# TH8_AFE.net
KiCad netlist of a schematic drawn in Altium Designer
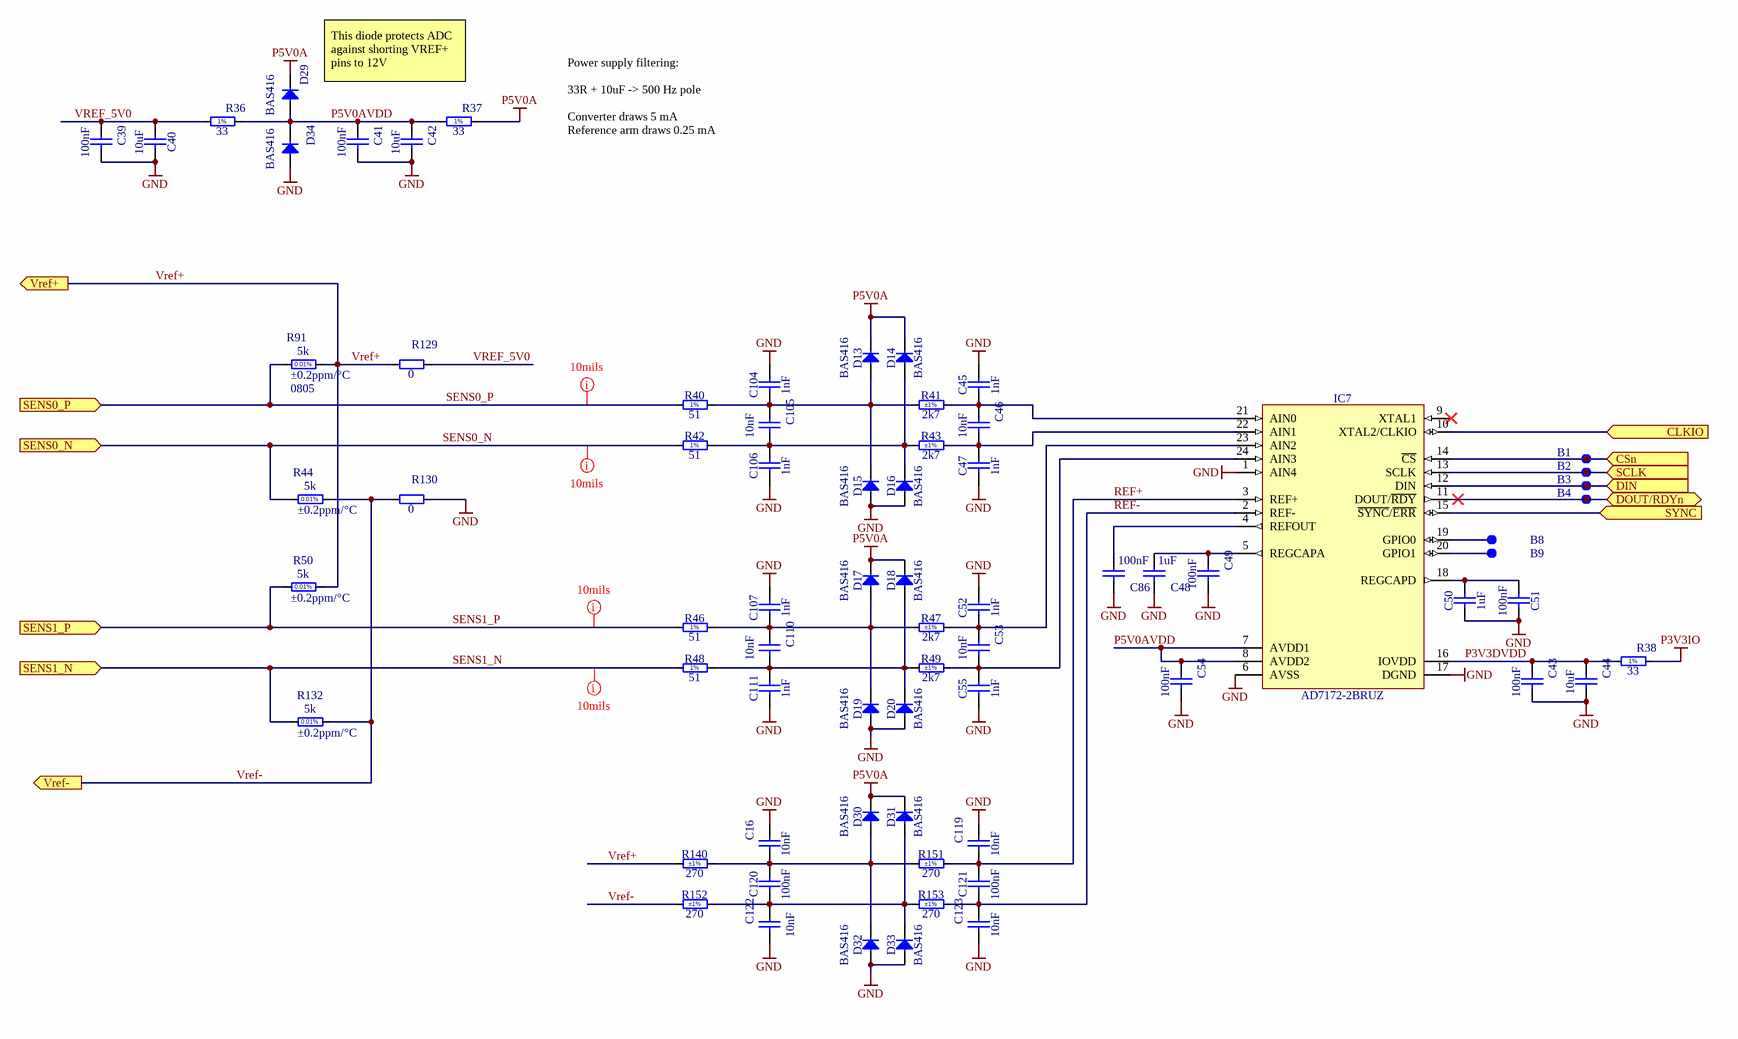
[diagram p0: TH8_AFE.SchDoc]

(export (version "E")
  (design (tool "Eeschema 10.0.6"))
  (components
    (comp (ref "B1")
      (value "SMD Pad")
      (footprint "C100")
      (description "Through Hole Pad")
      (fields (field (name "PART NUMBER") "SMD_PAD_D1MM") (field (name "AUTHOR") "CERN DEM JLC"))
      (libsource (lib "Eletro-mechanical") (part "Single SMD Pad (Round)"))
    )
    (comp (ref "B2")
      (value "SMD Pad")
      (footprint "C100")
      (description "Through Hole Pad")
      (fields (field (name "PART NUMBER") "SMD_PAD_D1MM") (field (name "AUTHOR") "CERN DEM JLC"))
      (libsource (lib "Eletro-mechanical") (part "Single SMD Pad (Round)"))
    )
    (comp (ref "B3")
      (value "SMD Pad")
      (footprint "C100")
      (description "Through Hole Pad")
      (fields (field (name "PART NUMBER") "SMD_PAD_D1MM") (field (name "AUTHOR") "CERN DEM JLC"))
      (libsource (lib "Eletro-mechanical") (part "Single SMD Pad (Round)"))
    )
    (comp (ref "B4")
      (value "SMD Pad")
      (footprint "C100")
      (description "Through Hole Pad")
      (fields (field (name "PART NUMBER") "SMD_PAD_D1MM") (field (name "AUTHOR") "CERN DEM JLC"))
      (libsource (lib "Eletro-mechanical") (part "Single SMD Pad (Round)"))
    )
    (comp (ref "B8")
      (value "SMD Pad")
      (footprint "C100")
      (description "Through Hole Pad")
      (fields (field (name "PART NUMBER") "SMD_PAD_D1MM") (field (name "AUTHOR") "CERN DEM JLC"))
      (libsource (lib "Eletro-mechanical") (part "Single SMD Pad (Round)"))
    )
    (comp (ref "B9")
      (value "SMD Pad")
      (footprint "C100")
      (description "Through Hole Pad")
      (fields (field (name "PART NUMBER") "SMD_PAD_D1MM") (field (name "AUTHOR") "CERN DEM JLC"))
      (libsource (lib "Eletro-mechanical") (part "Single SMD Pad (Round)"))
    )
    (comp (ref "C16")
      (value "10nF")
      (footprint "CAPC1608X87N")
      (description "Non-polarised capacitor")
      (fields
        (field (name "PART NUMBER") "CC0603_10NF_50V_5%_C0G")
        (field (name "VOLTAGE") "50V")
        (field (name "AUTHOR") "CERN DEM JLC")
      )
      (libsource (lib "Capacitors") (part "Capacitor - non polarized"))
    )
    (comp (ref "C39")
      (value "100nF")
      (footprint "CAPC1005X55N")
      (description "Non-polarised capacitor")
      (fields
        (field (name "PART NUMBER") "CC0402_100NF_16V_10%_X5R")
        (field (name "VOLTAGE") "16V")
        (field (name "AUTHOR") "CERN DEM JLC")
      )
      (libsource (lib "Capacitors") (part "Capacitor - non polarized"))
    )
    (comp (ref "C40")
      (value "10uF")
      (footprint "CAPC2012X135N")
      (description "Non-polarised capacitor")
      (fields
        (field (name "PART NUMBER") "CC0805_10UF_16V_10%_X5R")
        (field (name "VOLTAGE") "16V")
        (field (name "AUTHOR") "CERN DEM JLC")
      )
      (libsource (lib "Capacitors") (part "Capacitor - non polarized"))
    )
    (comp (ref "C41")
      (value "100nF")
      (footprint "CAPC1005X55N")
      (description "Non-polarised capacitor")
      (fields
        (field (name "PART NUMBER") "CC0402_100NF_16V_10%_X5R")
        (field (name "VOLTAGE") "16V")
        (field (name "AUTHOR") "CERN DEM JLC")
      )
      (libsource (lib "Capacitors") (part "Capacitor - non polarized"))
    )
    (comp (ref "C42")
      (value "10uF")
      (footprint "CAPC2012X135N")
      (description "Non-polarised capacitor")
      (fields
        (field (name "PART NUMBER") "CC0805_10UF_16V_10%_X5R")
        (field (name "VOLTAGE") "16V")
        (field (name "AUTHOR") "CERN DEM JLC")
      )
      (libsource (lib "Capacitors") (part "Capacitor - non polarized"))
    )
    (comp (ref "C43")
      (value "100nF")
      (footprint "CAPC1005X55N")
      (description "Non-polarised capacitor")
      (fields
        (field (name "PART NUMBER") "CC0402_100NF_16V_10%_X5R")
        (field (name "VOLTAGE") "16V")
        (field (name "AUTHOR") "CERN DEM JLC")
      )
      (libsource (lib "Capacitors") (part "Capacitor - non polarized"))
    )
    (comp (ref "C44")
      (value "10uF")
      (footprint "CAPC2012X135N")
      (description "Non-polarised capacitor")
      (fields
        (field (name "PART NUMBER") "CC0805_10UF_16V_10%_X5R")
        (field (name "VOLTAGE") "16V")
        (field (name "AUTHOR") "CERN DEM JLC")
      )
      (libsource (lib "Capacitors") (part "Capacitor - non polarized"))
    )
    (comp (ref "C45")
      (value "1nF")
      (footprint "CAPC1608X90N")
      (description "Non-polarised capacitor")
      (fields
        (field (name "PART NUMBER") "CC0603_1NF_50V_5%_NP0")
        (field (name "VOLTAGE") "50V")
        (field (name "AUTHOR") "CERN DEM JLC")
      )
      (libsource (lib "Capacitors") (part "Capacitor - non polarized"))
    )
    (comp (ref "C46")
      (value "10nF")
      (footprint "CAPC1608X87N")
      (description "Non-polarised capacitor")
      (fields
        (field (name "PART NUMBER") "CC0603_10NF_50V_5%_C0G")
        (field (name "VOLTAGE") "50V")
        (field (name "AUTHOR") "CERN DEM JLC")
      )
      (libsource (lib "Capacitors") (part "Capacitor - non polarized"))
    )
    (comp (ref "C47")
      (value "1nF")
      (footprint "CAPC1608X90N")
      (description "Non-polarised capacitor")
      (fields
        (field (name "PART NUMBER") "CC0603_1NF_50V_5%_NP0")
        (field (name "VOLTAGE") "50V")
        (field (name "AUTHOR") "CERN DEM JLC")
      )
      (libsource (lib "Capacitors") (part "Capacitor - non polarized"))
    )
    (comp (ref "C48")
      (value "1uF")
      (footprint "CAPC1608X87N")
      (description "Non-polarised capacitor")
      (fields
        (field (name "PART NUMBER") "CC0603_1UF_25V_10%_X7R")
        (field (name "VOLTAGE") "25V")
        (field (name "AUTHOR") "CERN DEM JLC")
      )
      (libsource (lib "Capacitors") (part "Capacitor - non polarized"))
    )
    (comp (ref "C49")
      (value "100nF")
      (footprint "CAPC1005X55N")
      (description "Non-polarised capacitor")
      (fields
        (field (name "PART NUMBER") "CC0402_100NF_16V_10%_X5R")
        (field (name "VOLTAGE") "16V")
        (field (name "AUTHOR") "CERN DEM JLC")
      )
      (libsource (lib "Capacitors") (part "Capacitor - non polarized"))
    )
    (comp (ref "C50")
      (value "1uF")
      (footprint "CAPC1608X87N")
      (description "Non-polarised capacitor")
      (fields
        (field (name "PART NUMBER") "CC0603_1UF_25V_10%_X7R")
        (field (name "VOLTAGE") "25V")
        (field (name "AUTHOR") "CERN DEM JLC")
      )
      (libsource (lib "Capacitors") (part "Capacitor - non polarized"))
    )
    (comp (ref "C51")
      (value "100nF")
      (footprint "CAPC1005X55N")
      (description "Non-polarised capacitor")
      (fields
        (field (name "PART NUMBER") "CC0402_100NF_16V_10%_X5R")
        (field (name "VOLTAGE") "16V")
        (field (name "AUTHOR") "CERN DEM JLC")
      )
      (libsource (lib "Capacitors") (part "Capacitor - non polarized"))
    )
    (comp (ref "C52")
      (value "1nF")
      (footprint "CAPC1608X90N")
      (description "Non-polarised capacitor")
      (fields
        (field (name "PART NUMBER") "CC0603_1NF_50V_5%_NP0")
        (field (name "VOLTAGE") "50V")
        (field (name "AUTHOR") "CERN DEM JLC")
      )
      (libsource (lib "Capacitors") (part "Capacitor - non polarized"))
    )
    (comp (ref "C53")
      (value "10nF")
      (footprint "CAPC1608X87N")
      (description "Non-polarised capacitor")
      (fields
        (field (name "PART NUMBER") "CC0603_10NF_50V_5%_C0G")
        (field (name "VOLTAGE") "50V")
        (field (name "AUTHOR") "CERN DEM JLC")
      )
      (libsource (lib "Capacitors") (part "Capacitor - non polarized"))
    )
    (comp (ref "C54")
      (value "100nF")
      (footprint "CAPC1005X55N")
      (description "Non-polarised capacitor")
      (fields
        (field (name "PART NUMBER") "CC0402_100NF_16V_10%_X5R")
        (field (name "VOLTAGE") "16V")
        (field (name "AUTHOR") "CERN DEM JLC")
      )
      (libsource (lib "Capacitors") (part "Capacitor - non polarized"))
    )
    (comp (ref "C55")
      (value "1nF")
      (footprint "CAPC1608X90N")
      (description "Non-polarised capacitor")
      (fields
        (field (name "PART NUMBER") "CC0603_1NF_50V_5%_NP0")
        (field (name "VOLTAGE") "50V")
        (field (name "AUTHOR") "CERN DEM JLC")
      )
      (libsource (lib "Capacitors") (part "Capacitor - non polarized"))
    )
    (comp (ref "C86")
      (value "100nF")
      (footprint "CAPC1005X55N")
      (description "Non-polarised capacitor")
      (fields
        (field (name "PART NUMBER") "CC0402_100NF_16V_10%_X5R")
        (field (name "VOLTAGE") "16V")
        (field (name "AUTHOR") "CERN DEM JLC")
      )
      (libsource (lib "Capacitors") (part "Capacitor - non polarized"))
    )
    (comp (ref "C104")
      (value "1nF")
      (footprint "CAPC1608X90N")
      (description "Non-polarised capacitor")
      (fields
        (field (name "PART NUMBER") "CC0603_1NF_50V_5%_NP0")
        (field (name "VOLTAGE") "50V")
        (field (name "AUTHOR") "CERN DEM JLC")
      )
      (libsource (lib "Capacitors") (part "Capacitor - non polarized"))
    )
    (comp (ref "C105")
      (value "10nF")
      (footprint "CAPC1608X87N")
      (description "Non-polarised capacitor")
      (fields
        (field (name "PART NUMBER") "CC0603_10NF_50V_5%_C0G")
        (field (name "VOLTAGE") "50V")
        (field (name "AUTHOR") "CERN DEM JLC")
      )
      (libsource (lib "Capacitors") (part "Capacitor - non polarized"))
    )
    (comp (ref "C106")
      (value "1nF")
      (footprint "CAPC1608X90N")
      (description "Non-polarised capacitor")
      (fields
        (field (name "PART NUMBER") "CC0603_1NF_50V_5%_NP0")
        (field (name "VOLTAGE") "50V")
        (field (name "AUTHOR") "CERN DEM JLC")
      )
      (libsource (lib "Capacitors") (part "Capacitor - non polarized"))
    )
    (comp (ref "C107")
      (value "1nF")
      (footprint "CAPC1608X90N")
      (description "Non-polarised capacitor")
      (fields
        (field (name "PART NUMBER") "CC0603_1NF_50V_5%_NP0")
        (field (name "VOLTAGE") "50V")
        (field (name "AUTHOR") "CERN DEM JLC")
      )
      (libsource (lib "Capacitors") (part "Capacitor - non polarized"))
    )
    (comp (ref "C110")
      (value "10nF")
      (footprint "CAPC1608X87N")
      (description "Non-polarised capacitor")
      (fields
        (field (name "PART NUMBER") "CC0603_10NF_50V_5%_C0G")
        (field (name "VOLTAGE") "50V")
        (field (name "AUTHOR") "CERN DEM JLC")
      )
      (libsource (lib "Capacitors") (part "Capacitor - non polarized"))
    )
    (comp (ref "C111")
      (value "1nF")
      (footprint "CAPC1608X90N")
      (description "Non-polarised capacitor")
      (fields
        (field (name "PART NUMBER") "CC0603_1NF_50V_5%_NP0")
        (field (name "VOLTAGE") "50V")
        (field (name "AUTHOR") "CERN DEM JLC")
      )
      (libsource (lib "Capacitors") (part "Capacitor - non polarized"))
    )
    (comp (ref "C119")
      (value "10nF")
      (footprint "CAPC1608X87N")
      (description "Non-polarised capacitor")
      (fields
        (field (name "PART NUMBER") "CC0603_10NF_50V_5%_C0G")
        (field (name "VOLTAGE") "50V")
        (field (name "AUTHOR") "CERN DEM JLC")
      )
      (libsource (lib "Capacitors") (part "Capacitor - non polarized"))
    )
    (comp (ref "C120")
      (value "100nF")
      (footprint "CAPC1608X87N")
      (description "Non-polarised capacitor")
      (fields
        (field (name "PART NUMBER") "CC0603_100NF_50V_10%_X5R")
        (field (name "VOLTAGE") "50V")
        (field (name "AUTHOR") "CERN DEM MR")
      )
      (libsource (lib "Capacitors") (part "Capacitor - non polarized"))
    )
    (comp (ref "C121")
      (value "100nF")
      (footprint "CAPC1608X87N")
      (description "Non-polarised capacitor")
      (fields
        (field (name "PART NUMBER") "CC0603_100NF_50V_10%_X5R")
        (field (name "VOLTAGE") "50V")
        (field (name "AUTHOR") "CERN DEM MR")
      )
      (libsource (lib "Capacitors") (part "Capacitor - non polarized"))
    )
    (comp (ref "C122")
      (value "10nF")
      (footprint "CAPC1608X87N")
      (description "Non-polarised capacitor")
      (fields
        (field (name "PART NUMBER") "CC0603_10NF_50V_5%_C0G")
        (field (name "VOLTAGE") "50V")
        (field (name "AUTHOR") "CERN DEM JLC")
      )
      (libsource (lib "Capacitors") (part "Capacitor - non polarized"))
    )
    (comp (ref "C123")
      (value "10nF")
      (footprint "CAPC1608X87N")
      (description "Non-polarised capacitor")
      (fields
        (field (name "PART NUMBER") "CC0603_10NF_50V_5%_C0G")
        (field (name "VOLTAGE") "50V")
        (field (name "AUTHOR") "CERN DEM JLC")
      )
      (libsource (lib "Capacitors") (part "Capacitor - non polarized"))
    )
    (comp (ref "D13")
      (value "BAS416")
      (footprint "SOD2512X110N")
      (description "Diode")
      (fields
        (field (name "VOLTAGE") "75V")
        (field (name "POWER") "200mA")
        (field (name "AUTHOR") "CERN DEM JLC")
      )
      (libsource (lib "ICs And Semiconductors") (part "Diode"))
    )
    (comp (ref "D14")
      (value "BAS416")
      (footprint "SOD2512X110N")
      (description "Diode")
      (fields
        (field (name "VOLTAGE") "75V")
        (field (name "POWER") "200mA")
        (field (name "AUTHOR") "CERN DEM JLC")
      )
      (libsource (lib "ICs And Semiconductors") (part "Diode"))
    )
    (comp (ref "D15")
      (value "BAS416")
      (footprint "SOD2512X110N")
      (description "Diode")
      (fields
        (field (name "VOLTAGE") "75V")
        (field (name "POWER") "200mA")
        (field (name "AUTHOR") "CERN DEM JLC")
      )
      (libsource (lib "ICs And Semiconductors") (part "Diode"))
    )
    (comp (ref "D16")
      (value "BAS416")
      (footprint "SOD2512X110N")
      (description "Diode")
      (fields
        (field (name "VOLTAGE") "75V")
        (field (name "POWER") "200mA")
        (field (name "AUTHOR") "CERN DEM JLC")
      )
      (libsource (lib "ICs And Semiconductors") (part "Diode"))
    )
    (comp (ref "D17")
      (value "BAS416")
      (footprint "SOD2512X110N")
      (description "Diode")
      (fields
        (field (name "VOLTAGE") "75V")
        (field (name "POWER") "200mA")
        (field (name "AUTHOR") "CERN DEM JLC")
      )
      (libsource (lib "ICs And Semiconductors") (part "Diode"))
    )
    (comp (ref "D18")
      (value "BAS416")
      (footprint "SOD2512X110N")
      (description "Diode")
      (fields
        (field (name "VOLTAGE") "75V")
        (field (name "POWER") "200mA")
        (field (name "AUTHOR") "CERN DEM JLC")
      )
      (libsource (lib "ICs And Semiconductors") (part "Diode"))
    )
    (comp (ref "D19")
      (value "BAS416")
      (footprint "SOD2512X110N")
      (description "Diode")
      (fields
        (field (name "VOLTAGE") "75V")
        (field (name "POWER") "200mA")
        (field (name "AUTHOR") "CERN DEM JLC")
      )
      (libsource (lib "ICs And Semiconductors") (part "Diode"))
    )
    (comp (ref "D20")
      (value "BAS416")
      (footprint "SOD2512X110N")
      (description "Diode")
      (fields
        (field (name "VOLTAGE") "75V")
        (field (name "POWER") "200mA")
        (field (name "AUTHOR") "CERN DEM JLC")
      )
      (libsource (lib "ICs And Semiconductors") (part "Diode"))
    )
    (comp (ref "D29")
      (value "BAS416")
      (footprint "SOD2512X110N")
      (description "Diode")
      (fields
        (field (name "VOLTAGE") "75V")
        (field (name "POWER") "200mA")
        (field (name "AUTHOR") "CERN DEM JLC")
      )
      (libsource (lib "ICs And Semiconductors") (part "Diode"))
    )
    (comp (ref "D30")
      (value "BAS416")
      (footprint "SOD2512X110N")
      (description "Diode")
      (fields
        (field (name "VOLTAGE") "75V")
        (field (name "POWER") "200mA")
        (field (name "AUTHOR") "CERN DEM JLC")
      )
      (libsource (lib "ICs And Semiconductors") (part "Diode"))
    )
    (comp (ref "D31")
      (value "BAS416")
      (footprint "SOD2512X110N")
      (description "Diode")
      (fields
        (field (name "VOLTAGE") "75V")
        (field (name "POWER") "200mA")
        (field (name "AUTHOR") "CERN DEM JLC")
      )
      (libsource (lib "ICs And Semiconductors") (part "Diode"))
    )
    (comp (ref "D32")
      (value "BAS416")
      (footprint "SOD2512X110N")
      (description "Diode")
      (fields
        (field (name "VOLTAGE") "75V")
        (field (name "POWER") "200mA")
        (field (name "AUTHOR") "CERN DEM JLC")
      )
      (libsource (lib "ICs And Semiconductors") (part "Diode"))
    )
    (comp (ref "D33")
      (value "BAS416")
      (footprint "SOD2512X110N")
      (description "Diode")
      (fields
        (field (name "VOLTAGE") "75V")
        (field (name "POWER") "200mA")
        (field (name "AUTHOR") "CERN DEM JLC")
      )
      (libsource (lib "ICs And Semiconductors") (part "Diode"))
    )
    (comp (ref "D34")
      (value "BAS416")
      (footprint "SOD2512X110N")
      (description "Diode")
      (fields
        (field (name "VOLTAGE") "75V")
        (field (name "POWER") "200mA")
        (field (name "AUTHOR") "CERN DEM JLC")
      )
      (libsource (lib "ICs And Semiconductors") (part "Diode"))
    )
    (comp (ref "IC7")
      (value "AD7172-2BRUZ")
      (footprint "SOP65P640X120-24N")
      (description "32-Bit, 10 kSPS, Sigma-Delta ADC with 100 µs Settling and True Rail-to-Rail Buffers")
      (fields (field (name "MANUFACTURER") "ANALOG DEVICES") (field (name "AUTHOR") "GK"))
      (libsource (lib "LIBRARY_SCH") (part "ADC_AD7172-2"))
    )
    (comp (ref "R36")
      (value "33")
      (footprint "RESC1005X40N")
      (description "Resistor - 1%")
      (fields
        (field (name "PART NUMBER") "R0402_33R_1%_0.0625W_100PPM")
        (field (name "POWER") "0.0625W")
        (field (name "AUTHOR") "CERN DEM JLC")
      )
      (libsource (lib "Resistors") (part "Resistor - 1%"))
    )
    (comp (ref "R37")
      (value "33")
      (footprint "RESC1005X40N")
      (description "Resistor - 1%")
      (fields
        (field (name "PART NUMBER") "R0402_33R_1%_0.0625W_100PPM")
        (field (name "POWER") "0.0625W")
        (field (name "AUTHOR") "CERN DEM JLC")
      )
      (libsource (lib "Resistors") (part "Resistor - 1%"))
    )
    (comp (ref "R38")
      (value "33")
      (footprint "RESC1005X40N")
      (description "Resistor - 1%")
      (fields
        (field (name "PART NUMBER") "R0402_33R_1%_0.0625W_100PPM")
        (field (name "POWER") "0.0625W")
        (field (name "AUTHOR") "CERN DEM JLC")
      )
      (libsource (lib "Resistors") (part "Resistor - 1%"))
    )
    (comp (ref "R40")
      (value "51")
      (footprint "RESC1005X40N")
      (description "Resistor - 1%")
      (fields
        (field (name "PART NUMBER") "R0402_51R_1%_0.0625W_100PPM")
        (field (name "POWER") "0.0625W")
        (field (name "AUTHOR") "CERN DEM JLC")
      )
      (libsource (lib "Resistors") (part "Resistor - 1%"))
    )
    (comp (ref "R41")
      (value "2k7")
      (footprint "RESC1005X40N")
      (description "Resistor - 1%")
      (fields
        (field (name "TOLERANCE") "±1%")
        (field (name "PART NUMBER") "R0402_2K7_1%_0.0625W_100PPM")
        (field (name "POWER") "0.0625W")
        (field (name "AUTHOR") "CERN DEM JLC")
      )
      (libsource (lib "Resistors") (part "Resistor - 1%"))
    )
    (comp (ref "R42")
      (value "51")
      (footprint "RESC1005X40N")
      (description "Resistor - 1%")
      (fields
        (field (name "PART NUMBER") "R0402_51R_1%_0.0625W_100PPM")
        (field (name "POWER") "0.0625W")
        (field (name "AUTHOR") "CERN DEM JLC")
      )
      (libsource (lib "Resistors") (part "Resistor - 1%"))
    )
    (comp (ref "R43")
      (value "2k7")
      (footprint "RESC1005X40N")
      (description "Resistor - 1%")
      (fields
        (field (name "TOLERANCE") "±1%")
        (field (name "PART NUMBER") "R0402_2K7_1%_0.0625W_100PPM")
        (field (name "POWER") "0.0625W")
        (field (name "AUTHOR") "CERN DEM JLC")
      )
      (libsource (lib "Resistors") (part "Resistor - 1%"))
    )
    (comp (ref "R44")
      (value "5k")
      (footprint "RESC2013X64N")
      (description "Resistor - 0.01%")
      (fields
        (field (name "PART NUMBER") "R0805_5K_0.01%_0.2W_0.2PPM_VISHAY_VSMP")
        (field (name "POWER") "0.2W")
        (field (name "TC") "±0.2ppm/°C")
        (field (name "AUTHOR") "CERN DEM JLC")
      )
      (libsource (lib "Resistors") (part "Resistor - 0.01%"))
    )
    (comp (ref "R46")
      (value "51")
      (footprint "RESC1005X40N")
      (description "Resistor - 1%")
      (fields
        (field (name "PART NUMBER") "R0402_51R_1%_0.0625W_100PPM")
        (field (name "POWER") "0.0625W")
        (field (name "AUTHOR") "CERN DEM JLC")
      )
      (libsource (lib "Resistors") (part "Resistor - 1%"))
    )
    (comp (ref "R47")
      (value "2k7")
      (footprint "RESC1005X40N")
      (description "Resistor - 1%")
      (fields
        (field (name "TOLERANCE") "±1%")
        (field (name "PART NUMBER") "R0402_2K7_1%_0.0625W_100PPM")
        (field (name "POWER") "0.0625W")
        (field (name "AUTHOR") "CERN DEM JLC")
      )
      (libsource (lib "Resistors") (part "Resistor - 1%"))
    )
    (comp (ref "R48")
      (value "51")
      (footprint "RESC1005X40N")
      (description "Resistor - 1%")
      (fields
        (field (name "PART NUMBER") "R0402_51R_1%_0.0625W_100PPM")
        (field (name "POWER") "0.0625W")
        (field (name "AUTHOR") "CERN DEM JLC")
      )
      (libsource (lib "Resistors") (part "Resistor - 1%"))
    )
    (comp (ref "R49")
      (value "2k7")
      (footprint "RESC1005X40N")
      (description "Resistor - 1%")
      (fields
        (field (name "TOLERANCE") "±1%")
        (field (name "PART NUMBER") "R0402_2K7_1%_0.0625W_100PPM")
        (field (name "POWER") "0.0625W")
        (field (name "AUTHOR") "CERN DEM JLC")
      )
      (libsource (lib "Resistors") (part "Resistor - 1%"))
    )
    (comp (ref "R50")
      (value "5k")
      (footprint "RESC2013X64N")
      (description "Resistor - 0.01%")
      (fields
        (field (name "PART NUMBER") "R0805_5K_0.01%_0.2W_0.2PPM_VISHAY_VSMP")
        (field (name "POWER") "0.2W")
        (field (name "TC") "±0.2ppm/°C")
        (field (name "AUTHOR") "CERN DEM JLC")
      )
      (libsource (lib "Resistors") (part "Resistor - 0.01%"))
    )
    (comp (ref "R91")
      (value "5k")
      (footprint "RESC2013X64N")
      (description "Resistor - 0.01%")
      (fields
        (field (name "PART NUMBER") "R0805_5K_0.01%_0.2W_0.2PPM_VISHAY_VSMP")
        (field (name "POWER") "0.2W")
        (field (name "TC") "±0.2ppm/°C")
        (field (name "CASE") "0805")
        (field (name "AUTHOR") "CERN DEM JLC")
      )
      (libsource (lib "Resistors") (part "Resistor - 0.01%"))
    )
    (comp (ref "R129")
      (value "0")
      (footprint "RESC1608X55N")
      (description "Resistor")
      (fields
        (field (name "PART NUMBER") "R0603_0R_JUMPER")
        (field (name "MANUFACTURER") "GENERIC")
        (field (name "AUTHOR") "CERN DEM JLC")
      )
      (libsource (lib "Resistors") (part "Resistor"))
    )
    (comp (ref "R130")
      (value "0")
      (footprint "RESC1608X55N")
      (description "Resistor")
      (fields
        (field (name "PART NUMBER") "R0603_0R_JUMPER")
        (field (name "MANUFACTURER") "GENERIC")
        (field (name "AUTHOR") "CERN DEM JLC")
      )
      (libsource (lib "Resistors") (part "Resistor"))
    )
    (comp (ref "R132")
      (value "5k")
      (footprint "RESC2013X64N")
      (description "Resistor - 0.01%")
      (fields
        (field (name "PART NUMBER") "R0805_5K_0.01%_0.2W_0.2PPM_VISHAY_VSMP")
        (field (name "POWER") "0.2W")
        (field (name "TC") "±0.2ppm/°C")
        (field (name "AUTHOR") "CERN DEM JLC")
      )
      (libsource (lib "Resistors") (part "Resistor - 0.01%"))
    )
    (comp (ref "R140")
      (value "270")
      (footprint "RESC1005X40N")
      (description "Resistor - 1%")
      (fields
        (field (name "TOLERANCE") "±1%")
        (field (name "PART NUMBER") "R0402_270R_1%_0.0625W_100PPM")
        (field (name "POWER") "0.0625W")
        (field (name "AUTHOR") "CERN DEM JLC")
      )
      (libsource (lib "Resistors") (part "Resistor - 1%"))
    )
    (comp (ref "R151")
      (value "270")
      (footprint "RESC1005X40N")
      (description "Resistor - 1%")
      (fields
        (field (name "TOLERANCE") "±1%")
        (field (name "PART NUMBER") "R0402_270R_1%_0.0625W_100PPM")
        (field (name "POWER") "0.0625W")
        (field (name "AUTHOR") "CERN DEM JLC")
      )
      (libsource (lib "Resistors") (part "Resistor - 1%"))
    )
    (comp (ref "R152")
      (value "270")
      (footprint "RESC1005X40N")
      (description "Resistor - 1%")
      (fields
        (field (name "TOLERANCE") "±1%")
        (field (name "PART NUMBER") "R0402_270R_1%_0.0625W_100PPM")
        (field (name "POWER") "0.0625W")
        (field (name "AUTHOR") "CERN DEM JLC")
      )
      (libsource (lib "Resistors") (part "Resistor - 1%"))
    )
    (comp (ref "R153")
      (value "270")
      (footprint "RESC1005X40N")
      (description "Resistor - 1%")
      (fields
        (field (name "TOLERANCE") "±1%")
        (field (name "PART NUMBER") "R0402_270R_1%_0.0625W_100PPM")
        (field (name "POWER") "0.0625W")
        (field (name "AUTHOR") "CERN DEM JLC")
      )
      (libsource (lib "Resistors") (part "Resistor - 1%"))
    )
  )
  (nets
    (net (code "1") (name "/CLKIO") (class "Default")
      (node (ref "IC7") (pin "10") (pinfunction "XTAL2/CLKIO_10") (pintype "bidirectional"))
    )
    (net (code "2") (name "/CSn") (class "Default")
      (node (ref "B1") (pin "1") (pinfunction "1_1") (pintype "bidirectional"))
      (node (ref "IC7") (pin "14") (pinfunction "~{CS}_14") (pintype "input"))
    )
    (net (code "3") (name "/DIN") (class "Default")
      (node (ref "B3") (pin "1") (pinfunction "1_1") (pintype "bidirectional"))
      (node (ref "IC7") (pin "12") (pinfunction "DIN_12") (pintype "input"))
    )
    (net (code "4") (name "/DOUT{slash}RDYn") (class "Default")
      (node (ref "B4") (pin "1") (pinfunction "1_1") (pintype "bidirectional"))
      (node (ref "IC7") (pin "11") (pinfunction "DOUT/~{RDY}_11") (pintype "output"))
    )
    (net (code "5") (name "/P3V3DVDD") (class "Default")
      (node (ref "C43") (pin "1") (pinfunction "1_1") (pintype "passive"))
      (node (ref "C44") (pin "1") (pinfunction "1_1") (pintype "passive"))
      (node (ref "IC7") (pin "16") (pinfunction "IOVDD_16") (pintype "power_in"))
      (node (ref "R38") (pin "1") (pinfunction "1_1") (pintype "passive"))
    )
    (net (code "6") (name "/P5V0AVDD") (class "Default")
      (node (ref "C41") (pin "1") (pinfunction "1_1") (pintype "passive"))
      (node (ref "C42") (pin "1") (pinfunction "1_1") (pintype "passive"))
      (node (ref "C54") (pin "1") (pinfunction "1_1") (pintype "passive"))
      (node (ref "D29") (pin "2") (pinfunction "A_2") (pintype "passive"))
      (node (ref "D34") (pin "1") (pinfunction "C_1") (pintype "passive"))
      (node (ref "IC7") (pin "7") (pinfunction "AVDD1_7") (pintype "power_in"))
      (node (ref "IC7") (pin "8") (pinfunction "AVDD2_8") (pintype "power_in"))
      (node (ref "R36") (pin "2") (pinfunction "2_2") (pintype "passive"))
      (node (ref "R37") (pin "1") (pinfunction "1_1") (pintype "passive"))
    )
    (net (code "7") (name "/REF+") (class "Default")
      (node (ref "C119") (pin "1") (pinfunction "1_1") (pintype "passive"))
      (node (ref "C121") (pin "2") (pinfunction "2_2") (pintype "passive"))
      (node (ref "IC7") (pin "3") (pinfunction "REF+_3") (pintype "input"))
      (node (ref "R151") (pin "2") (pinfunction "2_2") (pintype "passive"))
    )
    (net (code "8") (name "/REF-") (class "Default")
      (node (ref "C121") (pin "1") (pinfunction "1_1") (pintype "passive"))
      (node (ref "C123") (pin "2") (pinfunction "2_2") (pintype "passive"))
      (node (ref "IC7") (pin "2") (pinfunction "REF-_2") (pintype "input"))
      (node (ref "R153") (pin "2") (pinfunction "2_2") (pintype "passive"))
    )
    (net (code "9") (name "/SCLK") (class "Default")
      (node (ref "B2") (pin "1") (pinfunction "1_1") (pintype "bidirectional"))
      (node (ref "IC7") (pin "13") (pinfunction "SCLK_13") (pintype "input"))
    )
    (net (code "10") (name "/SENS0_N") (class "Default")
      (node (ref "R42") (pin "1") (pinfunction "1_1") (pintype "passive"))
      (node (ref "R44") (pin "1") (pinfunction "1_1") (pintype "passive"))
    )
    (net (code "11") (name "/SENS0_P") (class "Default")
      (node (ref "R40") (pin "1") (pinfunction "1_1") (pintype "passive"))
      (node (ref "R91") (pin "1") (pinfunction "1_1") (pintype "passive"))
    )
    (net (code "12") (name "/SENS1_N") (class "Default")
      (node (ref "R132") (pin "1") (pinfunction "1_1") (pintype "passive"))
      (node (ref "R48") (pin "1") (pinfunction "1_1") (pintype "passive"))
    )
    (net (code "13") (name "/SENS1_P") (class "Default")
      (node (ref "R46") (pin "1") (pinfunction "1_1") (pintype "passive"))
      (node (ref "R50") (pin "1") (pinfunction "1_1") (pintype "passive"))
    )
    (net (code "14") (name "/SYNC") (class "Default")
      (node (ref "IC7") (pin "15") (pinfunction "~{SYNC}/~{ERR}_15") (pintype "bidirectional"))
    )
    (net (code "15") (name "/VREF_5V0") (class "Default")
      (node (ref "C39") (pin "1") (pinfunction "1_1") (pintype "passive"))
      (node (ref "C40") (pin "1") (pinfunction "1_1") (pintype "passive"))
      (node (ref "R129") (pin "2") (pinfunction "2_2") (pintype "passive"))
      (node (ref "R36") (pin "1") (pinfunction "1_1") (pintype "passive"))
    )
    (net (code "16") (name "/Vref+") (class "Default")
      (node (ref "R129") (pin "1") (pinfunction "1_1") (pintype "passive"))
      (node (ref "R140") (pin "1") (pinfunction "1_1") (pintype "passive"))
      (node (ref "R50") (pin "2") (pinfunction "2_2") (pintype "passive"))
      (node (ref "R91") (pin "2") (pinfunction "2_2") (pintype "passive"))
    )
    (net (code "17") (name "/Vref-") (class "Default")
      (node (ref "R130") (pin "1") (pinfunction "1_1") (pintype "passive"))
      (node (ref "R132") (pin "2") (pinfunction "2_2") (pintype "passive"))
      (node (ref "R152") (pin "1") (pinfunction "1_1") (pintype "passive"))
      (node (ref "R44") (pin "2") (pinfunction "2_2") (pintype "passive"))
    )
    (net (code "18") (name "GND") (class "Default")
      (node (ref "C104") (pin "2") (pinfunction "2_2") (pintype "passive"))
      (node (ref "C106") (pin "1") (pinfunction "1_1") (pintype "passive"))
      (node (ref "C107") (pin "2") (pinfunction "2_2") (pintype "passive"))
      (node (ref "C111") (pin "1") (pinfunction "1_1") (pintype "passive"))
      (node (ref "C119") (pin "2") (pinfunction "2_2") (pintype "passive"))
      (node (ref "C122") (pin "1") (pinfunction "1_1") (pintype "passive"))
      (node (ref "C123") (pin "1") (pinfunction "1_1") (pintype "passive"))
      (node (ref "C16") (pin "2") (pinfunction "2_2") (pintype "passive"))
      (node (ref "C39") (pin "2") (pinfunction "2_2") (pintype "passive"))
      (node (ref "C40") (pin "2") (pinfunction "2_2") (pintype "passive"))
      (node (ref "C41") (pin "2") (pinfunction "2_2") (pintype "passive"))
      (node (ref "C42") (pin "2") (pinfunction "2_2") (pintype "passive"))
      (node (ref "C43") (pin "2") (pinfunction "2_2") (pintype "passive"))
      (node (ref "C44") (pin "2") (pinfunction "2_2") (pintype "passive"))
      (node (ref "C45") (pin "2") (pinfunction "2_2") (pintype "passive"))
      (node (ref "C47") (pin "1") (pinfunction "1_1") (pintype "passive"))
      (node (ref "C48") (pin "1") (pinfunction "1_1") (pintype "passive"))
      (node (ref "C49") (pin "2") (pinfunction "2_2") (pintype "passive"))
      (node (ref "C50") (pin "1") (pinfunction "1_1") (pintype "passive"))
      (node (ref "C51") (pin "2") (pinfunction "2_2") (pintype "passive"))
      (node (ref "C52") (pin "2") (pinfunction "2_2") (pintype "passive"))
      (node (ref "C54") (pin "2") (pinfunction "2_2") (pintype "passive"))
      (node (ref "C55") (pin "1") (pinfunction "1_1") (pintype "passive"))
      (node (ref "C86") (pin "2") (pinfunction "2_2") (pintype "passive"))
      (node (ref "D15") (pin "2") (pinfunction "A_2") (pintype "passive"))
      (node (ref "D16") (pin "2") (pinfunction "A_2") (pintype "passive"))
      (node (ref "D19") (pin "2") (pinfunction "A_2") (pintype "passive"))
      (node (ref "D20") (pin "2") (pinfunction "A_2") (pintype "passive"))
      (node (ref "D32") (pin "2") (pinfunction "A_2") (pintype "passive"))
      (node (ref "D33") (pin "2") (pinfunction "A_2") (pintype "passive"))
      (node (ref "D34") (pin "2") (pinfunction "A_2") (pintype "passive"))
      (node (ref "IC7") (pin "1") (pinfunction "AIN4_1") (pintype "input"))
      (node (ref "IC7") (pin "17") (pinfunction "DGND_17") (pintype "power_in"))
      (node (ref "IC7") (pin "6") (pinfunction "AVSS_6") (pintype "power_in"))
      (node (ref "R130") (pin "2") (pinfunction "2_2") (pintype "passive"))
    )
    (net (code "19") (name "Net-(D13-A)") (class "Default")
      (node (ref "C104") (pin "1") (pinfunction "1_1") (pintype "passive"))
      (node (ref "C105") (pin "1") (pinfunction "1_1") (pintype "passive"))
      (node (ref "D13") (pin "2") (pinfunction "A_2") (pintype "passive"))
      (node (ref "D15") (pin "1") (pinfunction "C_1") (pintype "passive"))
      (node (ref "R40") (pin "2") (pinfunction "2_2") (pintype "passive"))
      (node (ref "R41") (pin "1") (pinfunction "1_1") (pintype "passive"))
    )
    (net (code "20") (name "Net-(D14-A)") (class "Default")
      (node (ref "C105") (pin "2") (pinfunction "2_2") (pintype "passive"))
      (node (ref "C106") (pin "2") (pinfunction "2_2") (pintype "passive"))
      (node (ref "D14") (pin "2") (pinfunction "A_2") (pintype "passive"))
      (node (ref "D16") (pin "1") (pinfunction "C_1") (pintype "passive"))
      (node (ref "R42") (pin "2") (pinfunction "2_2") (pintype "passive"))
      (node (ref "R43") (pin "1") (pinfunction "1_1") (pintype "passive"))
    )
    (net (code "21") (name "Net-(D17-A)") (class "Default")
      (node (ref "C107") (pin "1") (pinfunction "1_1") (pintype "passive"))
      (node (ref "C110") (pin "1") (pinfunction "1_1") (pintype "passive"))
      (node (ref "D17") (pin "2") (pinfunction "A_2") (pintype "passive"))
      (node (ref "D19") (pin "1") (pinfunction "C_1") (pintype "passive"))
      (node (ref "R46") (pin "2") (pinfunction "2_2") (pintype "passive"))
      (node (ref "R47") (pin "1") (pinfunction "1_1") (pintype "passive"))
    )
    (net (code "22") (name "Net-(D18-A)") (class "Default")
      (node (ref "C110") (pin "2") (pinfunction "2_2") (pintype "passive"))
      (node (ref "C111") (pin "2") (pinfunction "2_2") (pintype "passive"))
      (node (ref "D18") (pin "2") (pinfunction "A_2") (pintype "passive"))
      (node (ref "D20") (pin "1") (pinfunction "C_1") (pintype "passive"))
      (node (ref "R48") (pin "2") (pinfunction "2_2") (pintype "passive"))
      (node (ref "R49") (pin "1") (pinfunction "1_1") (pintype "passive"))
    )
    (net (code "23") (name "Net-(D30-A)") (class "Default")
      (node (ref "C120") (pin "2") (pinfunction "2_2") (pintype "passive"))
      (node (ref "C16") (pin "1") (pinfunction "1_1") (pintype "passive"))
      (node (ref "D30") (pin "2") (pinfunction "A_2") (pintype "passive"))
      (node (ref "D32") (pin "1") (pinfunction "C_1") (pintype "passive"))
      (node (ref "R140") (pin "2") (pinfunction "2_2") (pintype "passive"))
      (node (ref "R151") (pin "1") (pinfunction "1_1") (pintype "passive"))
    )
    (net (code "24") (name "Net-(D31-A)") (class "Default")
      (node (ref "C120") (pin "1") (pinfunction "1_1") (pintype "passive"))
      (node (ref "C122") (pin "2") (pinfunction "2_2") (pintype "passive"))
      (node (ref "D31") (pin "2") (pinfunction "A_2") (pintype "passive"))
      (node (ref "D33") (pin "1") (pinfunction "C_1") (pintype "passive"))
      (node (ref "R152") (pin "2") (pinfunction "2_2") (pintype "passive"))
      (node (ref "R153") (pin "1") (pinfunction "1_1") (pintype "passive"))
    )
    (net (code "25") (name "Net-(IC7-AIN0)") (class "Default")
      (node (ref "C45") (pin "1") (pinfunction "1_1") (pintype "passive"))
      (node (ref "C46") (pin "1") (pinfunction "1_1") (pintype "passive"))
      (node (ref "IC7") (pin "21") (pinfunction "AIN0_21") (pintype "input"))
      (node (ref "R41") (pin "2") (pinfunction "2_2") (pintype "passive"))
    )
    (net (code "26") (name "Net-(IC7-AIN1)") (class "Default")
      (node (ref "C46") (pin "2") (pinfunction "2_2") (pintype "passive"))
      (node (ref "C47") (pin "2") (pinfunction "2_2") (pintype "passive"))
      (node (ref "IC7") (pin "22") (pinfunction "AIN1_22") (pintype "input"))
      (node (ref "R43") (pin "2") (pinfunction "2_2") (pintype "passive"))
    )
    (net (code "27") (name "Net-(IC7-AIN2)") (class "Default")
      (node (ref "C52") (pin "1") (pinfunction "1_1") (pintype "passive"))
      (node (ref "C53") (pin "1") (pinfunction "1_1") (pintype "passive"))
      (node (ref "IC7") (pin "23") (pinfunction "AIN2_23") (pintype "input"))
      (node (ref "R47") (pin "2") (pinfunction "2_2") (pintype "passive"))
    )
    (net (code "28") (name "Net-(IC7-AIN3)") (class "Default")
      (node (ref "C53") (pin "2") (pinfunction "2_2") (pintype "passive"))
      (node (ref "C55") (pin "2") (pinfunction "2_2") (pintype "passive"))
      (node (ref "IC7") (pin "24") (pinfunction "AIN3_24") (pintype "input"))
      (node (ref "R49") (pin "2") (pinfunction "2_2") (pintype "passive"))
    )
    (net (code "29") (name "Net-(IC7-GPIO0)") (class "Default")
      (node (ref "B8") (pin "1") (pinfunction "1_1") (pintype "bidirectional"))
      (node (ref "IC7") (pin "19") (pinfunction "GPIO0_19") (pintype "bidirectional"))
    )
    (net (code "30") (name "Net-(IC7-GPIO1)") (class "Default")
      (node (ref "B9") (pin "1") (pinfunction "1_1") (pintype "bidirectional"))
      (node (ref "IC7") (pin "20") (pinfunction "GPIO1_20") (pintype "bidirectional"))
    )
    (net (code "31") (name "Net-(IC7-REFOUT)") (class "Default")
      (node (ref "C86") (pin "1") (pinfunction "1_1") (pintype "passive"))
      (node (ref "IC7") (pin "4") (pinfunction "REFOUT_4") (pintype "output"))
    )
    (net (code "32") (name "Net-(IC7-REGCAPA)") (class "Default")
      (node (ref "C48") (pin "2") (pinfunction "2_2") (pintype "passive"))
      (node (ref "C49") (pin "1") (pinfunction "1_1") (pintype "passive"))
      (node (ref "IC7") (pin "5") (pinfunction "REGCAPA_5") (pintype "output"))
    )
    (net (code "33") (name "Net-(IC7-REGCAPD)") (class "Default")
      (node (ref "C50") (pin "2") (pinfunction "2_2") (pintype "passive"))
      (node (ref "C51") (pin "1") (pinfunction "1_1") (pintype "passive"))
      (node (ref "IC7") (pin "18") (pinfunction "REGCAPD_18") (pintype "output"))
    )
    (net (code "34") (name "P3V3IO") (class "Default")
      (node (ref "R38") (pin "2") (pinfunction "2_2") (pintype "passive"))
    )
    (net (code "35") (name "P5V0A") (class "Default")
      (node (ref "D13") (pin "1") (pinfunction "C_1") (pintype "passive"))
      (node (ref "D14") (pin "1") (pinfunction "C_1") (pintype "passive"))
      (node (ref "D17") (pin "1") (pinfunction "C_1") (pintype "passive"))
      (node (ref "D18") (pin "1") (pinfunction "C_1") (pintype "passive"))
      (node (ref "D29") (pin "1") (pinfunction "C_1") (pintype "passive"))
      (node (ref "D30") (pin "1") (pinfunction "C_1") (pintype "passive"))
      (node (ref "D31") (pin "1") (pinfunction "C_1") (pintype "passive"))
      (node (ref "R37") (pin "2") (pinfunction "2_2") (pintype "passive"))
    )
    (net (code "36") (name "unconnected-(IC7-XTAL1-Pad9)") (class "Default")
      (node (ref "IC7") (pin "9") (pinfunction "XTAL1_9") (pintype "input+no_connect"))
    )
  )
)
